# Sheet1.net
KiCad netlist of a schematic drawn in Altium Designer
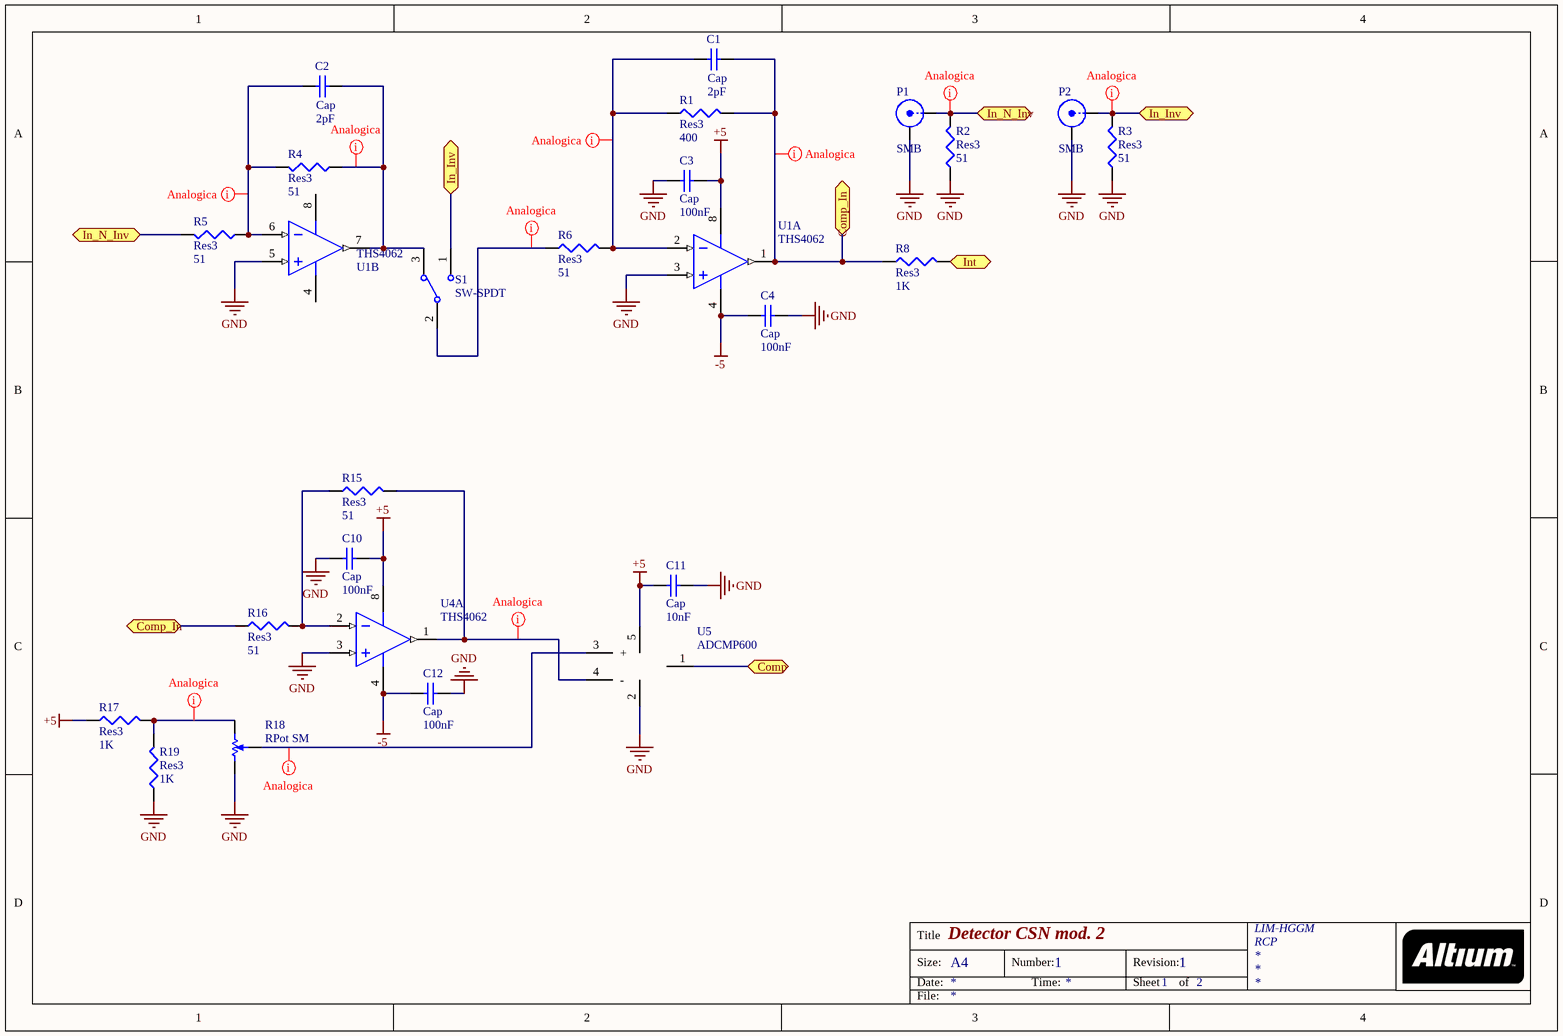
[diagram p0: Sheet1.SchDoc]

(export (version "E")
  (design (tool "Eeschema 10.0.6"))
  (components
    (comp (ref "C1")
      (value "Cap")
      (footprint "6-0805_N")
      (description "Capacitor")
      (fields (field (name "ALTIUM_VALUE") "2pF") (field (name "PUBLISHER") "Altium Limited"))
      (libsource (lib "Miscellaneous Devices") (part "Cap"))
    )
    (comp (ref "C2")
      (value "Cap")
      (footprint "6-0805_N")
      (description "Capacitor")
      (fields (field (name "ALTIUM_VALUE") "2pF") (field (name "PUBLISHER") "Altium Limited"))
      (libsource (lib "Miscellaneous Devices") (part "Cap"))
    )
    (comp (ref "C3")
      (value "Cap")
      (footprint "6-0805_N")
      (description "Capacitor")
      (fields (field (name "ALTIUM_VALUE") "100nF") (field (name "PUBLISHER") "Altium Limited"))
      (libsource (lib "Miscellaneous Devices") (part "Cap"))
    )
    (comp (ref "C4")
      (value "Cap")
      (footprint "6-0805_N")
      (description "Capacitor")
      (fields (field (name "ALTIUM_VALUE") "100nF") (field (name "PUBLISHER") "Altium Limited"))
      (libsource (lib "Miscellaneous Devices") (part "Cap"))
    )
    (comp (ref "C10")
      (value "Cap")
      (footprint "6-0805_N")
      (description "Capacitor")
      (fields (field (name "ALTIUM_VALUE") "100nF") (field (name "PUBLISHER") "Altium Limited"))
      (libsource (lib "Miscellaneous Devices") (part "Cap"))
    )
    (comp (ref "C11")
      (value "Cap")
      (footprint "6-0805_N")
      (description "Capacitor")
      (fields (field (name "ALTIUM_VALUE") "10nF") (field (name "PUBLISHER") "Altium Limited"))
      (libsource (lib "Miscellaneous Devices") (part "Cap"))
    )
    (comp (ref "C12")
      (value "Cap")
      (footprint "6-0805_N")
      (description "Capacitor")
      (fields (field (name "ALTIUM_VALUE") "100nF") (field (name "PUBLISHER") "Altium Limited"))
      (libsource (lib "Miscellaneous Devices") (part "Cap"))
    )
    (comp (ref "P1")
      (value "SMB")
      (footprint "SMB_V-RJ45")
      (description "SMB Straight Connector")
      (fields (field (name "PUBLISHER") "Altium Limited"))
      (libsource (lib "Miscellaneous Connectors") (part "SMB"))
    )
    (comp (ref "P2")
      (value "SMB")
      (footprint "SMB_V-RJ45")
      (description "SMB Straight Connector")
      (fields (field (name "PUBLISHER") "Altium Limited"))
      (libsource (lib "Miscellaneous Connectors") (part "SMB"))
    )
    (comp (ref "R1")
      (value "Res3")
      (footprint "6-0805_N")
      (description "Resistor")
      (fields (field (name "ALTIUM_VALUE") "400") (field (name "PUBLISHER") "Altium Limited"))
      (libsource (lib "Miscellaneous Devices") (part "Res3"))
    )
    (comp (ref "R2")
      (value "Res3")
      (footprint "6-0805_N")
      (description "Resistor")
      (fields (field (name "ALTIUM_VALUE") "51") (field (name "PUBLISHER") "Altium Limited"))
      (libsource (lib "Miscellaneous Devices") (part "Res3"))
    )
    (comp (ref "R3")
      (value "Res3")
      (footprint "6-0805_N")
      (description "Resistor")
      (fields (field (name "ALTIUM_VALUE") "51") (field (name "PUBLISHER") "Altium Limited"))
      (libsource (lib "Miscellaneous Devices") (part "Res3"))
    )
    (comp (ref "R4")
      (value "Res3")
      (footprint "6-0805_N")
      (description "Resistor")
      (fields (field (name "ALTIUM_VALUE") "51") (field (name "PUBLISHER") "Altium Limited"))
      (libsource (lib "Miscellaneous Devices") (part "Res3"))
    )
    (comp (ref "R5")
      (value "Res3")
      (footprint "6-0805_N")
      (description "Resistor")
      (fields (field (name "ALTIUM_VALUE") "51") (field (name "PUBLISHER") "Altium Limited"))
      (libsource (lib "Miscellaneous Devices") (part "Res3"))
    )
    (comp (ref "R6")
      (value "Res3")
      (footprint "6-0805_N")
      (description "Resistor")
      (fields (field (name "ALTIUM_VALUE") "51") (field (name "PUBLISHER") "Altium Limited"))
      (libsource (lib "Miscellaneous Devices") (part "Res3"))
    )
    (comp (ref "R8")
      (value "Res3")
      (footprint "6-0805_N")
      (description "Resistor")
      (fields (field (name "ALTIUM_VALUE") "1K") (field (name "PUBLISHER") "Altium Limited"))
      (libsource (lib "Miscellaneous Devices") (part "Res3"))
    )
    (comp (ref "R15")
      (value "Res3")
      (footprint "6-0805_N")
      (description "Resistor")
      (fields (field (name "ALTIUM_VALUE") "51") (field (name "PUBLISHER") "Altium Limited"))
      (libsource (lib "Miscellaneous Devices") (part "Res3"))
    )
    (comp (ref "R16")
      (value "Res3")
      (footprint "6-0805_N")
      (description "Resistor")
      (fields (field (name "ALTIUM_VALUE") "51") (field (name "PUBLISHER") "Altium Limited"))
      (libsource (lib "Miscellaneous Devices") (part "Res3"))
    )
    (comp (ref "R17")
      (value "Res3")
      (footprint "6-0805_N")
      (description "Resistor")
      (fields (field (name "ALTIUM_VALUE") "1K") (field (name "PUBLISHER") "Altium Limited"))
      (libsource (lib "Miscellaneous Devices") (part "Res3"))
    )
    (comp (ref "R18")
      (value "RPot SM")
      (footprint "POT4MM-2")
      (description "Square Trimming Potentiometer")
      (fields (field (name "PUBLISHER") "Altium Limited"))
      (libsource (lib "Miscellaneous Devices") (part "RPot SM"))
    )
    (comp (ref "R19")
      (value "Res3")
      (footprint "6-0805_N")
      (description "Resistor")
      (fields (field (name "ALTIUM_VALUE") "1K") (field (name "PUBLISHER") "Altium Limited"))
      (libsource (lib "Miscellaneous Devices") (part "Res3"))
    )
    (comp (ref "S1")
      (value "SW-SPDT")
      (footprint "HDR1X3")
      (description "SPDT Subminiature Toggle Switch, Right Angle Mounting, Vertical Actuation")
      (fields (field (name "PUBLISHER") "Altium Limited"))
      (libsource (lib "Miscellaneous Devices") (part "SW-SPDT"))
    )
    (comp (ref "U1")
      (value "THS4062")
      (footprint "S8_N")
      (description "Low Cost Dual Video Amplifier")
      (fields (field (name "PUBLISHER") "Altium Limited"))
      (libsource (lib "LT Video Amplifier") (part "LT1253CS8"))
    )
    (comp (ref "U4")
      (value "THS4062")
      (footprint "S8_N")
      (description "Low Cost Dual Video Amplifier")
      (fields (field (name "PUBLISHER") "Altium Limited"))
      (libsource (lib "LT Video Amplifier") (part "LT1253CS8"))
    )
    (comp (ref "U5") (value "ADCMP600") (footprint "SOT23-5_N") (libsource (lib "Schlib1") (part "ADCMP600")))
  )
  (nets
    (net (code "1") (name "+5") (class "Default")
      (node (ref "C10") (pin "2") (pinfunction "2_2") (pintype "passive"))
      (node (ref "C11") (pin "1") (pinfunction "1_1") (pintype "passive"))
      (node (ref "C3") (pin "2") (pinfunction "2_2") (pintype "passive"))
      (node (ref "R17") (pin "1") (pinfunction "1_1") (pintype "passive"))
      (node (ref "U1") (pin "8") (pinfunction "V+_8") (pintype "power_in"))
      (node (ref "U4") (pin "8") (pinfunction "V+_8") (pintype "power_in"))
      (node (ref "U5") (pin "5") (pintype "power_in"))
    )
    (net (code "2") (name "-5") (class "Default")
      (node (ref "C12") (pin "1") (pinfunction "1_1") (pintype "passive"))
      (node (ref "C4") (pin "1") (pinfunction "1_1") (pintype "passive"))
      (node (ref "U1") (pin "4") (pinfunction "V-_4") (pintype "power_in"))
      (node (ref "U4") (pin "4") (pinfunction "V-_4") (pintype "power_in"))
    )
    (net (code "3") (name "/Comp") (class "Default") (node (ref "U5") (pin "1") (pintype "passive")))
    (net (code "4") (name "/Comp_In") (class "Default")
      (node (ref "C1") (pin "2") (pinfunction "2_2") (pintype "passive"))
      (node (ref "R1") (pin "2") (pinfunction "2_2") (pintype "passive"))
      (node (ref "R16") (pin "1") (pinfunction "1_1") (pintype "passive"))
      (node (ref "R8") (pin "1") (pinfunction "1_1") (pintype "passive"))
      (node (ref "U1") (pin "1") (pinfunction "OUT_1") (pintype "output"))
    )
    (net (code "5") (name "/In_Inv") (class "Default")
      (node (ref "P2") (pin "1") (pinfunction "X_1") (pintype "passive"))
      (node (ref "R3") (pin "2") (pinfunction "2_2") (pintype "passive"))
      (node (ref "S1") (pin "1") (pinfunction "1_1") (pintype "passive"))
    )
    (net (code "6") (name "/In_N_Inv") (class "Default")
      (node (ref "P1") (pin "1") (pinfunction "X_1") (pintype "passive"))
      (node (ref "R2") (pin "2") (pinfunction "2_2") (pintype "passive"))
      (node (ref "R5") (pin "2") (pinfunction "2_2") (pintype "passive"))
    )
    (net (code "7") (name "/Int") (class "Default")
      (node (ref "R8") (pin "2") (pinfunction "2_2") (pintype "passive"))
    )
    (net (code "8") (name "GND") (class "Default")
      (node (ref "C10") (pin "1") (pinfunction "1_1") (pintype "passive"))
      (node (ref "C11") (pin "2") (pinfunction "2_2") (pintype "passive"))
      (node (ref "C12") (pin "2") (pinfunction "2_2") (pintype "passive"))
      (node (ref "C3") (pin "1") (pinfunction "1_1") (pintype "passive"))
      (node (ref "C4") (pin "2") (pinfunction "2_2") (pintype "passive"))
      (node (ref "P1") (pin "2") (pinfunction "Y_2") (pintype "passive"))
      (node (ref "P2") (pin "2") (pinfunction "Y_2") (pintype "passive"))
      (node (ref "R18") (pin "CCW") (pinfunction "-_CCW") (pintype "passive"))
      (node (ref "R19") (pin "1") (pinfunction "1_1") (pintype "passive"))
      (node (ref "R2") (pin "1") (pinfunction "1_1") (pintype "passive"))
      (node (ref "R3") (pin "1") (pinfunction "1_1") (pintype "passive"))
      (node (ref "U1") (pin "3") (pinfunction "IN+_3") (pintype "input"))
      (node (ref "U1") (pin "5") (pinfunction "IN+_5") (pintype "input"))
      (node (ref "U4") (pin "3") (pinfunction "IN+_3") (pintype "input"))
      (node (ref "U5") (pin "2") (pintype "power_in"))
    )
    (net (code "9") (name "Net-(R6-Pad1)") (class "Default")
      (node (ref "R6") (pin "1") (pinfunction "1_1") (pintype "passive"))
      (node (ref "S1") (pin "2") (pinfunction "2_2") (pintype "passive"))
    )
    (net (code "10") (name "Net-(R18-+)") (class "Default")
      (node (ref "R17") (pin "2") (pinfunction "2_2") (pintype "passive"))
      (node (ref "R18") (pin "CW") (pinfunction "+_CW") (pintype "passive"))
      (node (ref "R19") (pin "2") (pinfunction "2_2") (pintype "passive"))
    )
    (net (code "11") (name "Net-(U1A-IN-)") (class "Default")
      (node (ref "C1") (pin "1") (pinfunction "1_1") (pintype "passive"))
      (node (ref "R1") (pin "1") (pinfunction "1_1") (pintype "passive"))
      (node (ref "R6") (pin "2") (pinfunction "2_2") (pintype "passive"))
      (node (ref "U1") (pin "2") (pinfunction "IN-_2") (pintype "input"))
    )
    (net (code "12") (name "Net-(U1B-IN-)") (class "Default")
      (node (ref "C2") (pin "1") (pinfunction "1_1") (pintype "passive"))
      (node (ref "R4") (pin "2") (pinfunction "2_2") (pintype "passive"))
      (node (ref "R5") (pin "1") (pinfunction "1_1") (pintype "passive"))
      (node (ref "U1") (pin "6") (pinfunction "IN-_6") (pintype "input"))
    )
    (net (code "13") (name "Net-(U1B-OUT)") (class "Default")
      (node (ref "C2") (pin "2") (pinfunction "2_2") (pintype "passive"))
      (node (ref "R4") (pin "1") (pinfunction "1_1") (pintype "passive"))
      (node (ref "S1") (pin "3") (pinfunction "3_3") (pintype "passive"))
      (node (ref "U1") (pin "7") (pinfunction "OUT_7") (pintype "output"))
    )
    (net (code "14") (name "Net-(U4A-IN-)") (class "Default")
      (node (ref "R15") (pin "1") (pinfunction "1_1") (pintype "passive"))
      (node (ref "R16") (pin "2") (pinfunction "2_2") (pintype "passive"))
      (node (ref "U4") (pin "2") (pinfunction "IN-_2") (pintype "input"))
    )
    (net (code "15") (name "Net-(U4A-OUT)") (class "Default")
      (node (ref "R15") (pin "2") (pinfunction "2_2") (pintype "passive"))
      (node (ref "U4") (pin "1") (pinfunction "OUT_1") (pintype "output"))
      (node (ref "U5") (pin "4") (pinfunction "-_4") (pintype "passive"))
    )
    (net (code "16") (name "Net-(U5-+)") (class "Default")
      (node (ref "R18") (pin "W") (pinfunction "W_W") (pintype "passive"))
      (node (ref "U5") (pin "3") (pinfunction "+_3") (pintype "passive"))
    )
    (net (code "17") (name "unconnected-(U1B-V+-Pad8)") (class "Default")
      (node (ref "U1") (pin "8") (pinfunction "V+_8") (pintype "power_in"))
    )
    (net (code "18") (name "unconnected-(U1B-V--Pad4)") (class "Default")
      (node (ref "U1") (pin "4") (pinfunction "V-_4") (pintype "power_in"))
    )
  )
)
